# TallyLight.net
KiCad netlist of a schematic drawn in Altium Designer
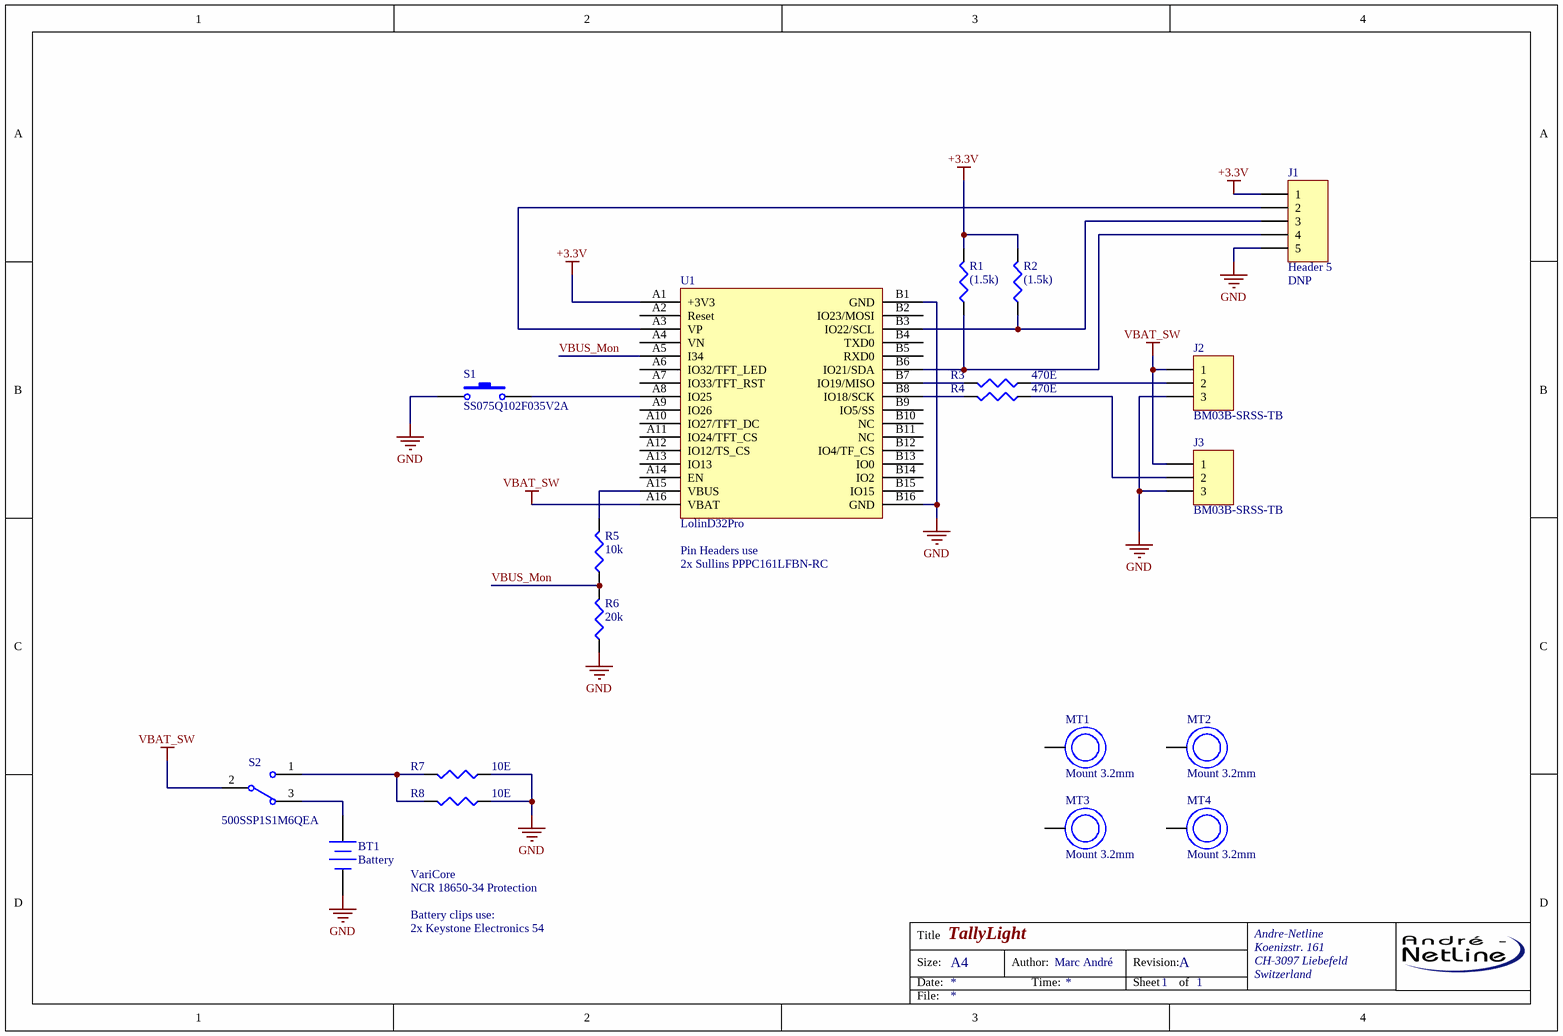
[diagram p0: TallyLight.SchDoc]

(export (version "E")
  (design (tool "Eeschema 10.0.6"))
  (components
    (comp (ref "BT1")
      (value "Battery")
      (footprint "Bat18650B")
      (description "Multicell Battery")
      (fields
        (field (name "MANUFACTURER") "Varicore")
        (field (name "MANUFACTURER PART NUMBER") "NCR 18650-34 Protection")
        (field (name "PUBLISHER") "Altium Limited")
      )
      (libsource (lib "Miscellaneous Devices") (part "Battery"))
    )
    (comp (ref "J1")
      (value "Header 5")
      (footprint "HDR1X5")
      (description "Header, 5-Pin")
      (fields (field (name "PUBLISHER") "Altium Limited"))
      (libsource (lib "Miscellaneous Connectors") (part "Header 5"))
    )
    (comp (ref "J2")
      (value "BM03B-SRSS-TB")
      (footprint "BM03B-SRSS-TB")
      (description "CONN HEADER SMD 3POS 1MM")
      (fields
        (field (name "MANUFACTURER") "JST")
        (field (name "MANUFACTURER PART NUMBER") "BM03B-SRSS-TB(LF)(SN)")
        (field (name "PUBLISHER") "Altium Limited")
      )
      (libsource (lib "Miscellaneous Connectors") (part "Header 3"))
    )
    (comp (ref "J3")
      (value "BM03B-SRSS-TB")
      (footprint "BM03B-SRSS-TB")
      (description "CONN HEADER SMD 3POS 1MM")
      (fields
        (field (name "MANUFACTURER") "JST")
        (field (name "MANUFACTURER PART NUMBER") "BM03B-SRSS-TB(LF)(SN)")
        (field (name "PUBLISHER") "Altium Limited")
      )
      (libsource (lib "Miscellaneous Connectors") (part "Header 3"))
    )
    (comp (ref "MT1")
      (value "Mount 3.2mm")
      (footprint "MT")
      (description "Mounting hole 3.2mm, 5.7mm pad")
      (libsource (lib "ColorSensorBoards") (part "MountingHole"))
    )
    (comp (ref "MT2")
      (value "Mount 3.2mm")
      (footprint "MT")
      (description "Mounting hole 3.2mm, 5.7mm pad")
      (libsource (lib "ColorSensorBoards") (part "MountingHole"))
    )
    (comp (ref "MT3")
      (value "Mount 3.2mm")
      (footprint "MT")
      (description "Mounting hole 3.2mm, 5.7mm pad")
      (libsource (lib "ColorSensorBoards") (part "MountingHole"))
    )
    (comp (ref "MT4")
      (value "Mount 3.2mm")
      (footprint "MT")
      (description "Mounting hole 3.2mm, 5.7mm pad")
      (libsource (lib "ColorSensorBoards") (part "MountingHole"))
    )
    (comp (ref "R1")
      (value "(1.5k)")
      (footprint "R0402")
      (description "RES SMD 1.5K OHM 1% 1/10W 0402")
      (fields
        (field (name "MANUFACTURER") "Panasonic")
        (field (name "MANUFACTURER PART NUMBER") "ERJ-2RKF1501X")
      )
      (libsource (lib "TallyLight") (part "RES 0402"))
    )
    (comp (ref "R2")
      (value "(1.5k)")
      (footprint "R0402")
      (description "RES SMD 1.5K OHM 1% 1/10W 0402")
      (fields
        (field (name "MANUFACTURER") "Panasonic")
        (field (name "MANUFACTURER PART NUMBER") "ERJ-2RKF1501X")
      )
      (libsource (lib "TallyLight") (part "RES 0402"))
    )
    (comp (ref "R3")
      (value "470E")
      (footprint "R0402")
      (description "RES SMD 470 OHM 1% 1/10W 0402")
      (fields
        (field (name "MANUFACTURER") "Panasonic")
        (field (name "MANUFACTURER PART NUMBER") "ERJ-2RKF4700X")
      )
      (libsource (lib "TallyLight") (part "RES 0402"))
    )
    (comp (ref "R4")
      (value "470E")
      (footprint "R0402")
      (description "RES SMD 470 OHM 1% 1/10W 0402")
      (fields
        (field (name "MANUFACTURER") "Panasonic")
        (field (name "MANUFACTURER PART NUMBER") "ERJ-2RKF4700X")
      )
      (libsource (lib "TallyLight") (part "RES 0402"))
    )
    (comp (ref "R5")
      (value "10k")
      (footprint "R0402")
      (description "RES SMD 10K OHM 1% 1/10W 0402")
      (fields
        (field (name "MANUFACTURER") "Panasonic")
        (field (name "MANUFACTURER PART NUMBER") "ERJ-2RKF1002X")
      )
      (libsource (lib "TallyLight") (part "RES 0402"))
    )
    (comp (ref "R6")
      (value "20k")
      (footprint "R0402")
      (description "RES SMD 20K OHM 1% 1/10W 0402")
      (fields
        (field (name "MANUFACTURER") "Panasonic")
        (field (name "MANUFACTURER PART NUMBER") "ERJ-2RKF2002X")
      )
      (libsource (lib "TallyLight") (part "RES 0402"))
    )
    (comp (ref "R7")
      (value "10E")
      (footprint "R0603")
      (description "RES 10 OHM 1% 1/10W 0603")
      (fields
        (field (name "MANUFACTURER") "Panasonic")
        (field (name "MANUFACTURER PART NUMBER") "Stackpole Electronics Inc")
      )
      (libsource (lib "TallyLight") (part "RES 0402"))
    )
    (comp (ref "R8")
      (value "10E")
      (footprint "R0603")
      (description "RES 10 OHM 1% 1/10W 0603")
      (fields
        (field (name "MANUFACTURER") "Panasonic")
        (field (name "MANUFACTURER PART NUMBER") "Stackpole Electronics Inc")
      )
      (libsource (lib "TallyLight") (part "RES 0402"))
    )
    (comp (ref "S1")
      (value "SS075Q102F035V2A")
      (footprint "SS075Q102F035V2A")
      (description "SWITCH SNAP ACT SPDT 100MA 125V")
      (fields (field (name "MANUFACTURER") "E-Switch") (field (name "PUBLISHER") "Altium Limited"))
      (libsource (lib "Miscellaneous Devices") (part "SW-PB"))
    )
    (comp (ref "S2")
      (value "500SSP1S1M6QEA")
      (footprint "500SSPxS2M6xEA")
      (description "SWITCH SLIDE SPDT 5A 120V")
      (fields (field (name "MANUFACTURER") "E-Switch") (field (name "PUBLISHER") "Altium Limited"))
      (libsource (lib "Miscellaneous Devices") (part "SW-SPDT"))
    )
    (comp (ref "U1")
      (value "LolinD32Pro")
      (footprint "LolinD32Pro")
      (description "ESP32 board")
      (fields (field (name "MANUFACTURER") "Wemos"))
      (libsource (lib "TallyLight") (part "LolinD32Pro"))
    )
  )
  (nets
    (net (code "1") (name "+3.3V") (class "Default")
      (node (ref "J1") (pin "1") (pinfunction "1_1") (pintype "passive"))
      (node (ref "R1") (pin "2") (pinfunction "2_2") (pintype "passive"))
      (node (ref "R2") (pin "2") (pinfunction "2_2") (pintype "passive"))
      (node (ref "U1") (pin "A1") (pinfunction "+3V3_A1") (pintype "passive"))
    )
    (net (code "2") (name "/VBUS_Mon") (class "Default")
      (node (ref "R5") (pin "1") (pinfunction "1_1") (pintype "passive"))
      (node (ref "R6") (pin "2") (pinfunction "2_2") (pintype "passive"))
      (node (ref "U1") (pin "A5") (pinfunction "I34_A5") (pintype "passive"))
    )
    (net (code "3") (name "GND") (class "Default")
      (node (ref "BT1") (pin "2") (pinfunction "-_2") (pintype "passive"))
      (node (ref "J1") (pin "5") (pinfunction "5_5") (pintype "passive"))
      (node (ref "J2") (pin "3") (pinfunction "3_3") (pintype "passive"))
      (node (ref "J3") (pin "3") (pinfunction "3_3") (pintype "passive"))
      (node (ref "R6") (pin "1") (pinfunction "1_1") (pintype "passive"))
      (node (ref "R7") (pin "1") (pinfunction "1_1") (pintype "passive"))
      (node (ref "R8") (pin "1") (pinfunction "1_1") (pintype "passive"))
      (node (ref "S1") (pin "1") (pinfunction "1_1") (pintype "passive"))
      (node (ref "U1") (pin "B1") (pinfunction "GND_B1") (pintype "passive"))
      (node (ref "U1") (pin "B16") (pinfunction "GND_B16") (pintype "passive"))
    )
    (net (code "4") (name "Net-(BT1-+)") (class "Default")
      (node (ref "BT1") (pin "1") (pinfunction "+_1") (pintype "passive"))
      (node (ref "S2") (pin "3") (pinfunction "3_3") (pintype "passive"))
    )
    (net (code "5") (name "Net-(J2-Pad2)") (class "Default")
      (node (ref "J2") (pin "2") (pinfunction "2_2") (pintype "passive"))
      (node (ref "R3") (pin "1") (pinfunction "1_1") (pintype "passive"))
    )
    (net (code "6") (name "Net-(J3-Pad2)") (class "Default")
      (node (ref "J3") (pin "2") (pinfunction "2_2") (pintype "passive"))
      (node (ref "R4") (pin "1") (pinfunction "1_1") (pintype "passive"))
    )
    (net (code "7") (name "Net-(R7-Pad2)") (class "Default")
      (node (ref "R7") (pin "2") (pinfunction "2_2") (pintype "passive"))
      (node (ref "R8") (pin "2") (pinfunction "2_2") (pintype "passive"))
      (node (ref "S2") (pin "1") (pinfunction "1_1") (pintype "passive"))
    )
    (net (code "8") (name "Net-(U1-IO18{slash}SCK)") (class "Default")
      (node (ref "R4") (pin "2") (pinfunction "2_2") (pintype "passive"))
      (node (ref "U1") (pin "B8") (pinfunction "IO18/SCK_B8") (pintype "passive"))
    )
    (net (code "9") (name "Net-(U1-IO19{slash}MISO)") (class "Default")
      (node (ref "R3") (pin "2") (pinfunction "2_2") (pintype "passive"))
      (node (ref "U1") (pin "B7") (pinfunction "IO19/MISO_B7") (pintype "passive"))
    )
    (net (code "10") (name "Net-(U1-IO21{slash}SDA)") (class "Default")
      (node (ref "J1") (pin "4") (pinfunction "4_4") (pintype "passive"))
      (node (ref "R1") (pin "1") (pinfunction "1_1") (pintype "passive"))
      (node (ref "U1") (pin "B6") (pinfunction "IO21/SDA_B6") (pintype "passive"))
    )
    (net (code "11") (name "Net-(U1-IO22{slash}SCL)") (class "Default")
      (node (ref "J1") (pin "3") (pinfunction "3_3") (pintype "passive"))
      (node (ref "R2") (pin "1") (pinfunction "1_1") (pintype "passive"))
      (node (ref "U1") (pin "B3") (pinfunction "IO22/SCL_B3") (pintype "passive"))
    )
    (net (code "12") (name "Net-(U1-IO25)") (class "Default")
      (node (ref "S1") (pin "2") (pinfunction "2_2") (pintype "passive"))
      (node (ref "U1") (pin "A8") (pinfunction "IO25_A8") (pintype "passive"))
    )
    (net (code "13") (name "Net-(U1-VBUS)") (class "Default")
      (node (ref "R5") (pin "2") (pinfunction "2_2") (pintype "passive"))
      (node (ref "U1") (pin "A15") (pinfunction "VBUS_A15") (pintype "passive"))
    )
    (net (code "14") (name "Net-(U1-VP)") (class "Default")
      (node (ref "J1") (pin "2") (pinfunction "2_2") (pintype "passive"))
      (node (ref "U1") (pin "A3") (pinfunction "VP_A3") (pintype "passive"))
    )
    (net (code "15") (name "VBAT_SW") (class "Default")
      (node (ref "J2") (pin "1") (pinfunction "1_1") (pintype "passive"))
      (node (ref "J3") (pin "1") (pinfunction "1_1") (pintype "passive"))
      (node (ref "S2") (pin "2") (pinfunction "2_2") (pintype "passive"))
      (node (ref "U1") (pin "A16") (pinfunction "VBAT_A16") (pintype "passive"))
    )
    (net (code "16") (name "unconnected-(MT1-Pad1)") (class "Default")
      (node (ref "MT1") (pin "1") (pintype "passive"))
    )
    (net (code "17") (name "unconnected-(MT2-Pad1)") (class "Default")
      (node (ref "MT2") (pin "1") (pintype "passive"))
    )
    (net (code "18") (name "unconnected-(MT3-Pad1)") (class "Default")
      (node (ref "MT3") (pin "1") (pintype "passive"))
    )
    (net (code "19") (name "unconnected-(MT4-Pad1)") (class "Default")
      (node (ref "MT4") (pin "1") (pintype "passive"))
    )
    (net (code "20") (name "unconnected-(U1-EN-PadA14)") (class "Default")
      (node (ref "U1") (pin "A14") (pinfunction "EN_A14") (pintype "passive"))
    )
    (net (code "21") (name "unconnected-(U1-IO0-PadB13)") (class "Default")
      (node (ref "U1") (pin "B13") (pinfunction "IO0_B13") (pintype "passive"))
    )
    (net (code "22") (name "unconnected-(U1-IO2-PadB14)") (class "Default")
      (node (ref "U1") (pin "B14") (pinfunction "IO2_B14") (pintype "passive"))
    )
    (net (code "23") (name "unconnected-(U1-IO4{slash}TF_CS-PadB12)") (class "Default")
      (node (ref "U1") (pin "B12") (pinfunction "IO4/TF_CS_B12") (pintype "passive"))
    )
    (net (code "24") (name "unconnected-(U1-IO5{slash}SS-PadB9)") (class "Default")
      (node (ref "U1") (pin "B9") (pinfunction "IO5/SS_B9") (pintype "passive"))
    )
    (net (code "25") (name "unconnected-(U1-IO12{slash}TS_CS-PadA12)") (class "Default")
      (node (ref "U1") (pin "A12") (pinfunction "IO12/TS_CS_A12") (pintype "passive"))
    )
    (net (code "26") (name "unconnected-(U1-IO13-PadA13)") (class "Default")
      (node (ref "U1") (pin "A13") (pinfunction "IO13_A13") (pintype "passive"))
    )
    (net (code "27") (name "unconnected-(U1-IO15-PadB15)") (class "Default")
      (node (ref "U1") (pin "B15") (pinfunction "IO15_B15") (pintype "passive"))
    )
    (net (code "28") (name "unconnected-(U1-IO23{slash}MOSI-PadB2)") (class "Default")
      (node (ref "U1") (pin "B2") (pinfunction "IO23/MOSI_B2") (pintype "passive"))
    )
    (net (code "29") (name "unconnected-(U1-IO24{slash}TFT_CS-PadA11)") (class "Default")
      (node (ref "U1") (pin "A11") (pinfunction "IO24/TFT_CS_A11") (pintype "passive"))
    )
    (net (code "30") (name "unconnected-(U1-IO26-PadA9)") (class "Default")
      (node (ref "U1") (pin "A9") (pinfunction "IO26_A9") (pintype "passive"))
    )
    (net (code "31") (name "unconnected-(U1-IO27{slash}TFT_DC-PadA10)") (class "Default")
      (node (ref "U1") (pin "A10") (pinfunction "IO27/TFT_DC_A10") (pintype "passive"))
    )
    (net (code "32") (name "unconnected-(U1-IO32{slash}TFT_LED-PadA6)") (class "Default")
      (node (ref "U1") (pin "A6") (pinfunction "IO32/TFT_LED_A6") (pintype "passive"))
    )
    (net (code "33") (name "unconnected-(U1-IO33{slash}TFT_RST-PadA7)") (class "Default")
      (node (ref "U1") (pin "A7") (pinfunction "IO33/TFT_RST_A7") (pintype "passive"))
    )
    (net (code "34") (name "unconnected-(U1-NC-PadB10)") (class "Default")
      (node (ref "U1") (pin "B10") (pinfunction "NC_B10") (pintype "passive"))
    )
    (net (code "35") (name "unconnected-(U1-NC-PadB11)") (class "Default")
      (node (ref "U1") (pin "B11") (pinfunction "NC_B11") (pintype "passive"))
    )
    (net (code "36") (name "unconnected-(U1-RXD0-PadB5)") (class "Default")
      (node (ref "U1") (pin "B5") (pinfunction "RXD0_B5") (pintype "passive"))
    )
    (net (code "37") (name "unconnected-(U1-Reset-PadA2)") (class "Default")
      (node (ref "U1") (pin "A2") (pinfunction "Reset_A2") (pintype "passive"))
    )
    (net (code "38") (name "unconnected-(U1-TXD0-PadB4)") (class "Default")
      (node (ref "U1") (pin "B4") (pinfunction "TXD0_B4") (pintype "passive"))
    )
    (net (code "39") (name "unconnected-(U1-VN-PadA4)") (class "Default")
      (node (ref "U1") (pin "A4") (pinfunction "VN_A4") (pintype "passive"))
    )
  )
)
